# nguyen_li.net
KiCad netlist of a schematic drawn in Altium Designer
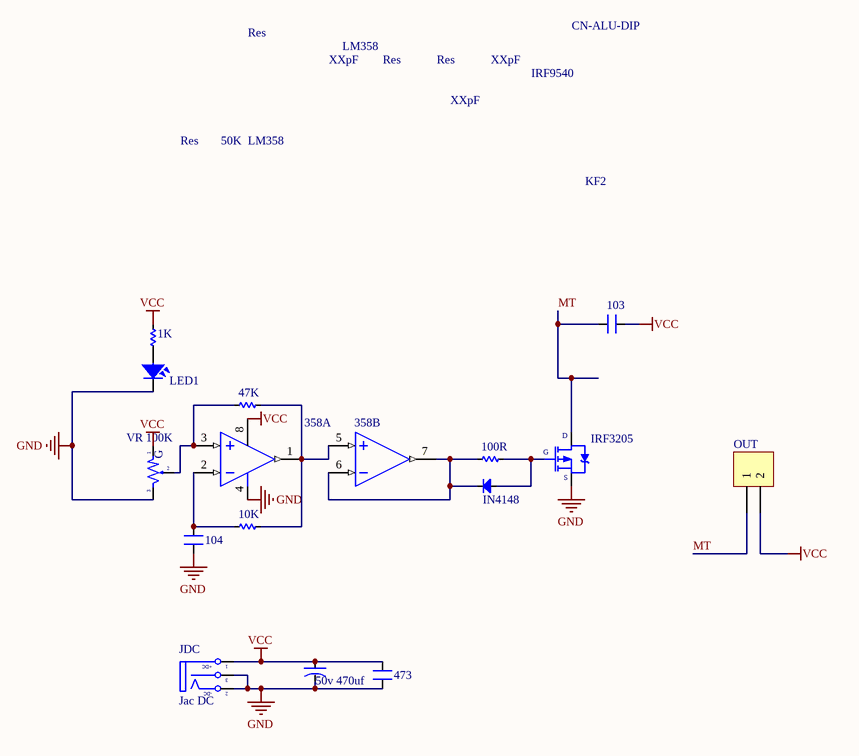
[diagram p0: nguyen li.SchDoc]

(export (version "E")
  (design (tool "Eeschema 10.0.6"))
  (components
    (comp (ref "1K")
      (value "Res")
      (footprint "RES-1/4W")
      (fields
        (field (name "MANUFACTURER") "Generic Components")
        (field (name "PUBLISHER") "Altium Hobart Technology Centre")
      )
      (libsource (lib "LIBRARY") (part "Res"))
    )
    (comp (ref "10K")
      (value "Res")
      (footprint "RES-1/4W")
      (fields
        (field (name "MANUFACTURER") "Generic Components")
        (field (name "PUBLISHER") "Altium Hobart Technology Centre")
      )
      (libsource (lib "LIBRARY") (part "Res"))
    )
    (comp (ref "47K")
      (value "Res")
      (footprint "RES-1/4W")
      (fields
        (field (name "MANUFACTURER") "Generic Components")
        (field (name "PUBLISHER") "Altium Hobart Technology Centre")
      )
      (libsource (lib "LIBRARY") (part "Res"))
    )
    (comp (ref "50v 470uf")
      (value "CN-ALU-DIP")
      (footprint "CA-ALU-8")
      (description "Capacitor (Semiconductor SIM Model)")
      (fields (field (name "PUBLISHER") "Altium Limited"))
      (libsource (lib "LIBRARY") (part "CN-ALU-DIP"))
    )
    (comp (ref "100R")
      (value "Res")
      (footprint "RES-1/4W")
      (fields
        (field (name "MANUFACTURER") "Generic Components")
        (field (name "PUBLISHER") "Altium Hobart Technology Centre")
      )
      (libsource (lib "LIBRARY") (part "Res"))
    )
    (comp (ref "103") (value "XXpF") (footprint "CN1") (libsource (lib "LIBRARY") (part "CN")))
    (comp (ref "104") (value "XXpF") (footprint "CN1.5") (libsource (lib "LIBRARY") (part "CN")))
    (comp (ref "358")
      (value "LM358")
      (footprint "DIP8")
      (description "Low-Power Dual Operational Amplifier")
      (libsource (lib "LIBRARY") (part "LM358"))
    )
    (comp (ref "473") (value "XXpF") (footprint "CN1.5") (libsource (lib "LIBRARY") (part "CN")))
    (comp (ref "IN4148")
      (value "Diode")
      (footprint "DIO-0.5A-SMALL")
      (description "Default Diode")
      (fields (field (name "PUBLISHER") "Altium Limited"))
      (libsource (lib "LIBRARY") (part "Diode"))
    )
    (comp (ref "IRF3205")
      (value "IRF9540")
      (footprint "TO220H1")
      (description "HEXFET P-Channel Power MOSFET")
      (libsource (lib "LIBRARY") (part "IRF9540"))
    )
    (comp (ref "JDC")
      (value "Jac DC")
      (footprint "DC0")
      (description "Jac DC input")
      (libsource (lib "LIBRARY") (part "DCIN"))
    )
    (comp (ref "LED1")
      (value "LED")
      (footprint "LED-5-RED")
      (description "LED Single colour Green and Red")
      (libsource (lib "LIBRARY") (part "LED"))
    )
    (comp (ref "OUT")
      (value "KF2")
      (footprint "KF2-3.5")
      (fields
        (field (name "MANUFACTURER") "Würth Elektronik eiSos GmbH")
        (field (name "PARTNO") "691103110002")
        (field (name "CREATED BY") "Karrer Zheng")
      )
      (libsource (lib "LIBRARY") (part "KF2"))
    )
    (comp (ref "VR 100K")
      (value "50K")
      (footprint "VR-S1")
      (description "Var Resistor")
      (libsource (lib "LIBRARY") (part "VR-S"))
    )
  )
  (nets
    (net (code "1") (name "/MT") (class "Default")
      (node (ref "103") (pin "1") (pinfunction "1_1") (pintype "passive"))
      (node (ref "IRF3205") (pin "2") (pinfunction "D_2") (pintype "passive"))
      (node (ref "OUT") (pin "1") (pinfunction "1_1") (pintype "passive"))
    )
    (net (code "2") (name "GND") (class "Default")
      (node (ref "104") (pin "1") (pinfunction "1_1") (pintype "passive"))
      (node (ref "358") (pin "4") (pinfunction "-V_4") (pintype "passive"))
      (node (ref "473") (pin "1") (pinfunction "1_1") (pintype "passive"))
      (node (ref "50v 470uf") (pin "2") (pinfunction "2_2") (pintype "passive"))
      (node (ref "IRF3205") (pin "3") (pinfunction "S_3") (pintype "passive"))
      (node (ref "JDC") (pin "2") (pinfunction "TN_2") (pintype "passive"))
      (node (ref "JDC") (pin "3") (pinfunction "S_3") (pintype "power_in"))
      (node (ref "LED1") (pin "2") (pinfunction "2_2") (pintype "passive"))
      (node (ref "VR 100K") (pin "3") (pinfunction "3_3") (pintype "passive"))
    )
    (net (code "3") (name "Net-(1K-Pad2)") (class "Default")
      (node (ref "1K") (pin "2") (pinfunction "2_2") (pintype "passive"))
      (node (ref "LED1") (pin "1") (pinfunction "1_1") (pintype "passive"))
    )
    (net (code "4") (name "Net-(358A-IN+)") (class "Default")
      (node (ref "358") (pin "3") (pinfunction "IN+_3") (pintype "input"))
      (node (ref "47K") (pin "2") (pinfunction "2_2") (pintype "passive"))
      (node (ref "VR 100K") (pin "2") (pinfunction "2_2") (pintype "passive"))
    )
    (net (code "5") (name "Net-(358A-IN-)") (class "Default")
      (node (ref "104") (pin "2") (pinfunction "2_2") (pintype "passive"))
      (node (ref "10K") (pin "2") (pinfunction "2_2") (pintype "passive"))
      (node (ref "358") (pin "2") (pinfunction "IN-_2") (pintype "input"))
    )
    (net (code "6") (name "Net-(358A-OUT)") (class "Default")
      (node (ref "10K") (pin "1") (pinfunction "1_1") (pintype "passive"))
      (node (ref "358") (pin "1") (pinfunction "OUT_1") (pintype "output"))
      (node (ref "358") (pin "5") (pinfunction "IN+_5") (pintype "input"))
      (node (ref "47K") (pin "1") (pinfunction "1_1") (pintype "passive"))
    )
    (net (code "7") (name "Net-(358B-IN-)") (class "Default")
      (node (ref "100R") (pin "2") (pinfunction "2_2") (pintype "passive"))
      (node (ref "358") (pin "6") (pinfunction "IN-_6") (pintype "input"))
      (node (ref "358") (pin "7") (pinfunction "OUT_7") (pintype "output"))
      (node (ref "IN4148") (pin "2") (pinfunction "K_2") (pintype "passive"))
    )
    (net (code "8") (name "Net-(IN4148-A)") (class "Default")
      (node (ref "100R") (pin "1") (pinfunction "1_1") (pintype "passive"))
      (node (ref "IN4148") (pin "1") (pinfunction "A_1") (pintype "passive"))
      (node (ref "IRF3205") (pin "1") (pinfunction "G_1") (pintype "passive"))
    )
    (net (code "9") (name "VCC") (class "Default")
      (node (ref "103") (pin "2") (pinfunction "2_2") (pintype "passive"))
      (node (ref "1K") (pin "1") (pinfunction "1_1") (pintype "passive"))
      (node (ref "358") (pin "8") (pinfunction "+V_8") (pintype "passive"))
      (node (ref "473") (pin "2") (pinfunction "2_2") (pintype "passive"))
      (node (ref "50v 470uf") (pin "1") (pinfunction "1_1") (pintype "passive"))
      (node (ref "JDC") (pin "1") (pinfunction "T_1") (pintype "passive"))
      (node (ref "OUT") (pin "2") (pinfunction "2_2") (pintype "passive"))
      (node (ref "VR 100K") (pin "1") (pinfunction "1_1") (pintype "passive"))
    )
  )
)
